# sendai.net
KiCad netlist of a schematic drawn in EAGLE
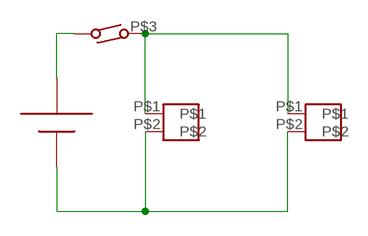
[diagram p0: schematic, sheet 1]

(export (version "E")
  (design (tool "Eeschema 10.0.6"))
  (components
    (comp (ref "U$1")
      (value "CR2032_CR2032")
      (footprint "eagle-import:CR2032_CR2032")
      (libsource (lib "eagle-import") (part "CR2032_CR2032"))
    )
    (comp (ref "U$2")
      (value "CONNECTER_CON2")
      (footprint "eagle-import:CONNECTER_CON2")
      (libsource (lib "eagle-import") (part "CONNECTER_CON2"))
    )
    (comp (ref "U$3")
      (value "CONNECTER_CON2")
      (footprint "eagle-import:CONNECTER_CON2")
      (libsource (lib "eagle-import") (part "CONNECTER_CON2"))
    )
    (comp (ref "U$4")
      (value "LEAD_SWITCH_LEAD_SWITCH")
      (footprint "eagle-import:LEAD_SWITCH_LEAD_SWITCH")
      (libsource (lib "eagle-import") (part "LEAD_SWITCH_LEAD_SWITCH"))
    )
  )
  (nets
    (net (code "1") (name "Net-(U$1--)") (class "Default")
      (node (ref "U$1") (pin "-1") (pinfunction "-_-1") (pintype "bidirectional"))
      (node (ref "U$2") (pin "P$2") (pinfunction "P$2_P$2") (pintype "bidirectional"))
      (node (ref "U$3") (pin "P$2") (pinfunction "P$2_P$2") (pintype "bidirectional"))
    )
    (net (code "2") (name "Net-(U$4-P$1)") (class "Default")
      (node (ref "U$2") (pin "P$1") (pinfunction "P$1_P$1") (pintype "bidirectional"))
      (node (ref "U$3") (pin "P$1") (pinfunction "P$1_P$1") (pintype "bidirectional"))
      (node (ref "U$4") (pin "P$3") (pinfunction "P$1_P$3") (pintype "bidirectional"))
    )
    (net (code "3") (name "Net-(U$4-P$2)") (class "Default")
      (node (ref "U$1") (pin "P$1") (pinfunction "+_P$1") (pintype "bidirectional"))
      (node (ref "U$1") (pin "P$2") (pinfunction "+_P$2") (pintype "bidirectional"))
      (node (ref "U$4") (pin "P$4") (pinfunction "P$2_P$4") (pintype "bidirectional"))
    )
  )
)
